# board.net
KiCad netlist of a schematic drawn in EAGLE
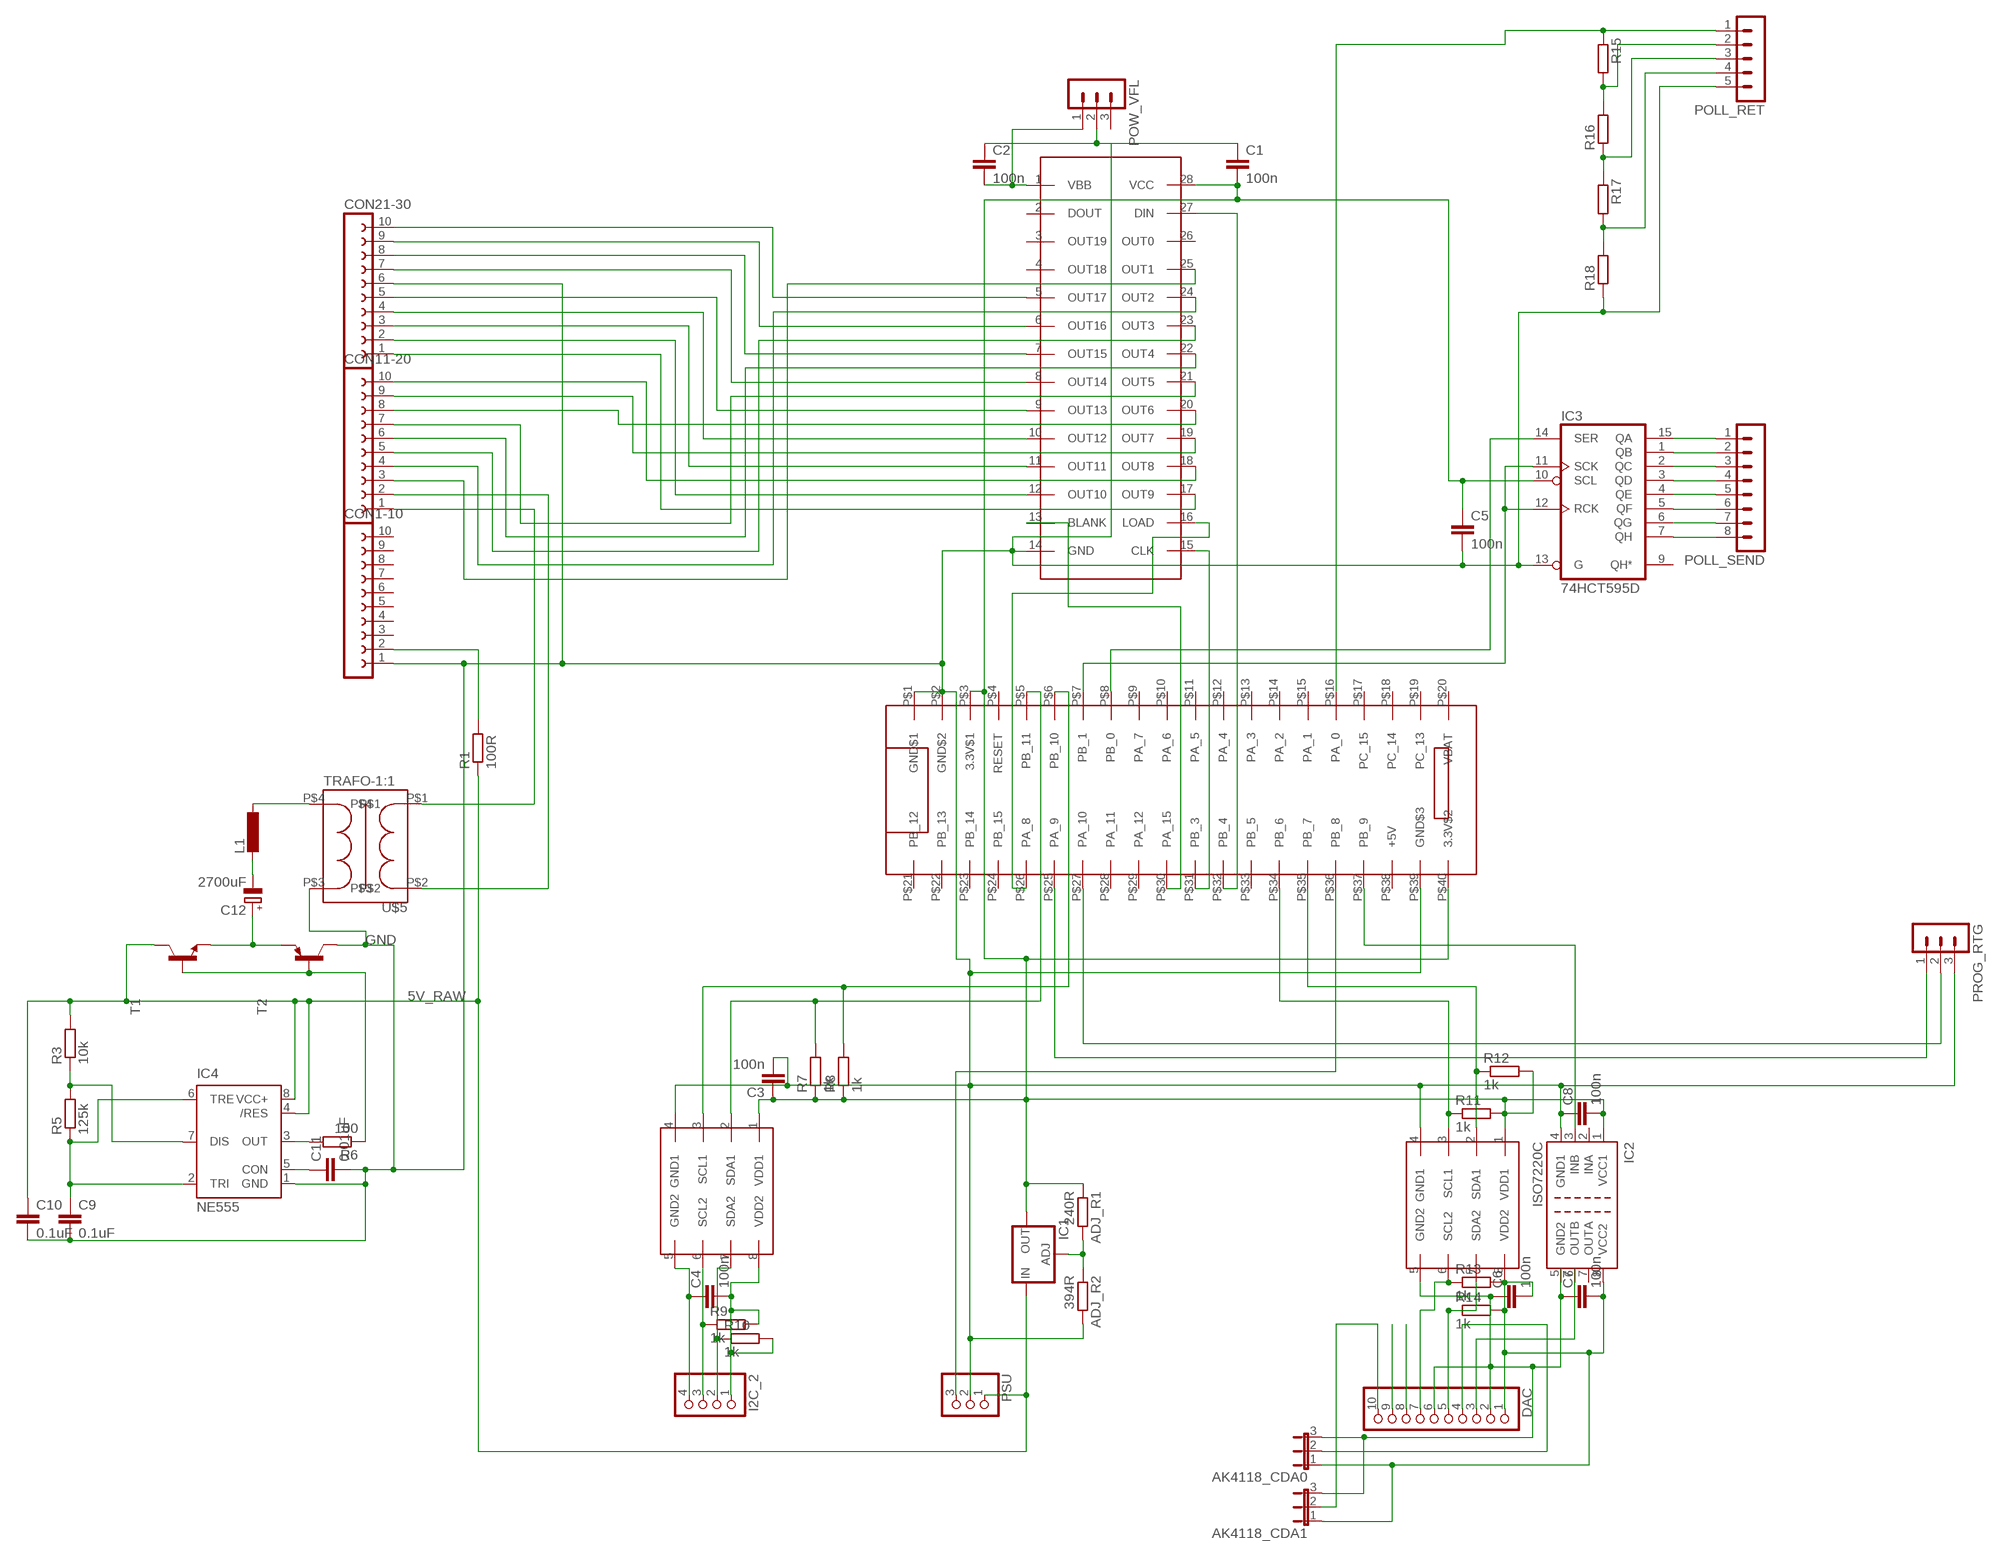
[diagram p0: schematic, sheet 1]

(export (version "E")
  (design (tool "Eeschema 10.0.6"))
  (components
    (comp (ref "ADJ_R1")
      (value "240R")
      (footprint "eagle-import:0207_10")
      (libsource (lib "eagle-import") (part "R-EU_0207/10"))
    )
    (comp (ref "ADJ_R2")
      (value "394R")
      (footprint "eagle-import:0207_10")
      (libsource (lib "eagle-import") (part "R-EU_0207/10"))
    )
    (comp (ref "AK4118_CDA0")
      (value "JP2E")
      (footprint "eagle-import:JP2")
      (libsource (lib "eagle-import") (part "JP2E"))
    )
    (comp (ref "AK4118_CDA1")
      (value "JP2E")
      (footprint "eagle-import:JP2")
      (libsource (lib "eagle-import") (part "JP2E"))
    )
    (comp (ref "C1")
      (value "100n")
      (footprint "eagle-import:C1206")
      (libsource (lib "eagle-import") (part "C-EUC1206"))
    )
    (comp (ref "C2")
      (value "100n")
      (footprint "eagle-import:C1206")
      (libsource (lib "eagle-import") (part "C-EUC1206"))
    )
    (comp (ref "C3")
      (value "100n")
      (footprint "eagle-import:C1206")
      (libsource (lib "eagle-import") (part "C-EUC1206"))
    )
    (comp (ref "C4")
      (value "100n")
      (footprint "eagle-import:C1206")
      (libsource (lib "eagle-import") (part "C-EUC1206"))
    )
    (comp (ref "C5")
      (value "100n")
      (footprint "eagle-import:C1206")
      (libsource (lib "eagle-import") (part "C-EUC1206"))
    )
    (comp (ref "C6")
      (value "100n")
      (footprint "eagle-import:C1206")
      (libsource (lib "eagle-import") (part "C-EUC1206"))
    )
    (comp (ref "C7")
      (value "100n")
      (footprint "eagle-import:C1210")
      (libsource (lib "eagle-import") (part "C-EUC1210"))
    )
    (comp (ref "C8")
      (value "100n")
      (footprint "eagle-import:C1210")
      (libsource (lib "eagle-import") (part "C-EUC1210"))
    )
    (comp (ref "C9")
      (value "0.1uF")
      (footprint "eagle-import:C1206")
      (libsource (lib "eagle-import") (part "C-EUC1206"))
    )
    (comp (ref "C10")
      (value "0.1uF")
      (footprint "eagle-import:C1206")
      (libsource (lib "eagle-import") (part "C-EUC1206"))
    )
    (comp (ref "C11")
      (value "0.01uF")
      (footprint "eagle-import:C1206")
      (libsource (lib "eagle-import") (part "C-EUC1206"))
    )
    (comp (ref "C12")
      (value "2700uF")
      (footprint "eagle-import:E3,5-8")
      (libsource (lib "eagle-import") (part "CPOL-EUE3.5-8"))
    )
    (comp (ref "CON1-10")
      (value "FE10-1")
      (footprint "eagle-import:FE10")
      (libsource (lib "eagle-import") (part "FE10-1"))
    )
    (comp (ref "CON11-20")
      (value "FE10-1")
      (footprint "eagle-import:FE10")
      (libsource (lib "eagle-import") (part "FE10-1"))
    )
    (comp (ref "CON21-30")
      (value "FE10-1")
      (footprint "eagle-import:FE10")
      (libsource (lib "eagle-import") (part "FE10-1"))
    )
    (comp (ref "DAC")
      (value "PINHD-1X10")
      (footprint "eagle-import:1X10")
      (libsource (lib "eagle-import") (part "PINHD-1X10"))
    )
    (comp (ref "I2C_2")
      (value "PINHD-1X4")
      (footprint "eagle-import:1X04")
      (libsource (lib "eagle-import") (part "PINHD-1X4"))
    )
    (comp (ref "IC1")
      (value "LM317TS")
      (footprint "eagle-import:317TS")
      (libsource (lib "eagle-import") (part "LM317TS"))
    )
    (comp (ref "IC2")
      (value "ISO7220C")
      (footprint "eagle-import:SO-08")
      (fields (field (name "MPN") "ISO7220CD"))
      (libsource (lib "eagle-import") (part "ISO7220C"))
    )
    (comp (ref "IC3")
      (value "74HCT595D")
      (footprint "eagle-import:SO16")
      (libsource (lib "eagle-import") (part "74595DHCT"))
    )
    (comp (ref "IC4")
      (value "NE555")
      (footprint "eagle-import:DIL-08")
      (fields (field (name "MF") "Arrow Electronics") (field (name "MPN") "NE555N"))
      (libsource (lib "eagle-import") (part "NE555"))
    )
    (comp (ref "L1")
      (value "L-EU0204/5")
      (footprint "eagle-import:0204_5")
      (libsource (lib "eagle-import") (part "L-EU0204/5"))
    )
    (comp (ref "POLL_RET")
      (value "MA05-1")
      (footprint "eagle-import:MA05-1")
      (libsource (lib "eagle-import") (part "MA05-1"))
    )
    (comp (ref "POLL_SEND")
      (value "MA08-1")
      (footprint "eagle-import:MA08-1")
      (libsource (lib "eagle-import") (part "MA08-1"))
    )
    (comp (ref "POW_VFL")
      (value "MA03-1")
      (footprint "eagle-import:MA03-1")
      (libsource (lib "eagle-import") (part "MA03-1"))
    )
    (comp (ref "PROG_RTG")
      (value "MA03-1")
      (footprint "eagle-import:MA03-1")
      (libsource (lib "eagle-import") (part "MA03-1"))
    )
    (comp (ref "PSU")
      (value "PINHD-1X3")
      (footprint "eagle-import:1X03")
      (libsource (lib "eagle-import") (part "PINHD-1X3"))
    )
    (comp (ref "R1")
      (value "100R")
      (footprint "eagle-import:0207_10")
      (libsource (lib "eagle-import") (part "R-EU_0207/10"))
    )
    (comp (ref "R3")
      (value "10k")
      (footprint "eagle-import:R1206")
      (libsource (lib "eagle-import") (part "R-EU_R1206"))
    )
    (comp (ref "R5")
      (value "125k")
      (footprint "eagle-import:R1206")
      (libsource (lib "eagle-import") (part "R-EU_R1206"))
    )
    (comp (ref "R6")
      (value "100")
      (footprint "eagle-import:R1206")
      (libsource (lib "eagle-import") (part "R-EU_R1206"))
    )
    (comp (ref "R7")
      (value "1k")
      (footprint "eagle-import:M1206")
      (libsource (lib "eagle-import") (part "R-EU_M1206"))
    )
    (comp (ref "R8")
      (value "1k")
      (footprint "eagle-import:M1206")
      (libsource (lib "eagle-import") (part "R-EU_M1206"))
    )
    (comp (ref "R9")
      (value "1k")
      (footprint "eagle-import:M1206")
      (libsource (lib "eagle-import") (part "R-EU_M1206"))
    )
    (comp (ref "R10")
      (value "1k")
      (footprint "eagle-import:M1206")
      (libsource (lib "eagle-import") (part "R-EU_M1206"))
    )
    (comp (ref "R11")
      (value "1k")
      (footprint "eagle-import:M1206")
      (libsource (lib "eagle-import") (part "R-EU_M1206"))
    )
    (comp (ref "R12")
      (value "1k")
      (footprint "eagle-import:M1206")
      (libsource (lib "eagle-import") (part "R-EU_M1206"))
    )
    (comp (ref "R13")
      (value "1k")
      (footprint "eagle-import:M1206")
      (libsource (lib "eagle-import") (part "R-EU_M1206"))
    )
    (comp (ref "R14")
      (value "1k")
      (footprint "eagle-import:M1206")
      (libsource (lib "eagle-import") (part "R-EU_M1206"))
    )
    (comp (ref "R15")
      (value "R-EU_M1206")
      (footprint "eagle-import:M1206")
      (libsource (lib "eagle-import") (part "R-EU_M1206"))
    )
    (comp (ref "R16")
      (value "R-EU_M1206")
      (footprint "eagle-import:M1206")
      (libsource (lib "eagle-import") (part "R-EU_M1206"))
    )
    (comp (ref "R17")
      (value "R-EU_M1206")
      (footprint "eagle-import:M1206")
      (libsource (lib "eagle-import") (part "R-EU_M1206"))
    )
    (comp (ref "R18")
      (value "R-EU_M1206")
      (footprint "eagle-import:M1206")
      (libsource (lib "eagle-import") (part "R-EU_M1206"))
    )
    (comp (ref "T1")
      (value "-NPN-TO92")
      (footprint "eagle-import:TO92")
      (libsource (lib "eagle-import") (part "-NPN-TO92"))
    )
    (comp (ref "T2")
      (value "-PNP-TO92")
      (footprint "eagle-import:TO92")
      (libsource (lib "eagle-import") (part "-PNP-TO92"))
    )
    (comp (ref "U$1")
      (value "ADUM1250")
      (footprint "eagle-import:SO8")
      (libsource (lib "eagle-import") (part "ADUM1250"))
    )
    (comp (ref "U$2")
      (value "ADUM1250")
      (footprint "eagle-import:SO8")
      (libsource (lib "eagle-import") (part "ADUM1250"))
    )
    (comp (ref "U$3")
      (value "STM32F103C8T6_BOARD")
      (footprint "eagle-import:STM32F103C8T6_BOARD")
      (libsource (lib "eagle-import") (part "STM32F103C8T6_BOARD"))
    )
    (comp (ref "U$4")
      (value "MAX6921AWI")
      (footprint "eagle-import:SO28L")
      (libsource (lib "eagle-import") (part "MAX6921AWI"))
    )
    (comp (ref "U$5")
      (value "TRAFO-1:1")
      (footprint "eagle-import:TRAFO-10-12.5")
      (libsource (lib "eagle-import") (part "TRAFO-1{colon}1"))
    )
  )
  (nets
    (net (code "1") (name "/5V_RAW") (class "Default")
      (node (ref "C10") (pin "1") (pinfunction "1_1") (pintype "passive"))
      (node (ref "IC1") (pin "3") (pinfunction "IN_3") (pintype "input"))
      (node (ref "IC4") (pin "4") (pinfunction "/RES_4") (pintype "input"))
      (node (ref "IC4") (pin "8") (pinfunction "VCC+_8") (pintype "power_in"))
      (node (ref "PSU") (pin "1") (pinfunction "1_1") (pintype "passive"))
      (node (ref "R1") (pin "1") (pinfunction "1_1") (pintype "passive"))
      (node (ref "R3") (pin "2") (pinfunction "2_2") (pintype "passive"))
      (node (ref "T1") (pin "3") (pinfunction "C_3") (pintype "passive"))
    )
    (net (code "2") (name "/GND") (class "Default")
      (node (ref "ADJ_R2") (pin "2") (pinfunction "2_2") (pintype "passive"))
      (node (ref "C1") (pin "1") (pinfunction "1_1") (pintype "passive"))
      (node (ref "C10") (pin "2") (pinfunction "2_2") (pintype "passive"))
      (node (ref "C11") (pin "2") (pinfunction "2_2") (pintype "passive"))
      (node (ref "C2") (pin "1") (pinfunction "1_1") (pintype "passive"))
      (node (ref "C3") (pin "2") (pinfunction "2_2") (pintype "passive"))
      (node (ref "C5") (pin "2") (pinfunction "2_2") (pintype "passive"))
      (node (ref "C8") (pin "1") (pinfunction "1_1") (pintype "passive"))
      (node (ref "C9") (pin "2") (pinfunction "2_2") (pintype "passive"))
      (node (ref "CON1-10") (pin "1") (pinfunction "1_1") (pintype "passive"))
      (node (ref "CON21-30") (pin "6") (pinfunction "6_6") (pintype "passive"))
      (node (ref "IC2") (pin "4") (pinfunction "GND1_4") (pintype "power_in"))
      (node (ref "IC3") (pin "13") (pinfunction "G_13") (pintype "input"))
      (node (ref "IC4") (pin "1") (pinfunction "GND_1") (pintype "power_in"))
      (node (ref "POLL_RET") (pin "5") (pinfunction "5_5") (pintype "passive"))
      (node (ref "POW_VFL") (pin "2") (pinfunction "2_2") (pintype "passive"))
      (node (ref "PROG_RTG") (pin "3") (pinfunction "3_3") (pintype "passive"))
      (node (ref "PSU") (pin "2") (pinfunction "2_2") (pintype "passive"))
      (node (ref "R18") (pin "1") (pinfunction "1_1") (pintype "passive"))
      (node (ref "T2") (pin "3") (pinfunction "C_3") (pintype "passive"))
      (node (ref "U$1") (pin "4") (pinfunction "GND1_4") (pintype "bidirectional"))
      (node (ref "U$2") (pin "4") (pinfunction "GND1_4") (pintype "bidirectional"))
      (node (ref "U$3") (pin "P$1") (pinfunction "GND$1_P$1") (pintype "bidirectional"))
      (node (ref "U$3") (pin "P$2") (pinfunction "GND$2_P$2") (pintype "bidirectional"))
      (node (ref "U$3") (pin "P$39") (pinfunction "GND$3_P$39") (pintype "bidirectional"))
      (node (ref "U$4") (pin "14") (pinfunction "GND_14") (pintype "bidirectional"))
      (node (ref "U$5") (pin "P$3") (pinfunction "P$3_P$3") (pintype "bidirectional"))
    )
    (net (code "3") (name "Net-(AK4118_CDA0-Pad2)") (class "Default")
      (node (ref "AK4118_CDA0") (pin "2") (pinfunction "2_2") (pintype "passive"))
      (node (ref "DAC") (pin "4") (pinfunction "4_4") (pintype "passive"))
    )
    (net (code "4") (name "Net-(AK4118_CDA1-Pad2)") (class "Default")
      (node (ref "AK4118_CDA1") (pin "2") (pinfunction "2_2") (pintype "passive"))
      (node (ref "DAC") (pin "10") (pinfunction "10_10") (pintype "passive"))
    )
    (net (code "5") (name "Net-(C12-Pad-)") (class "Default")
      (node (ref "C12") (pin "-") (pinfunction "-_-") (pintype "passive"))
      (node (ref "L1") (pin "2") (pinfunction "2_2") (pintype "passive"))
    )
    (net (code "6") (name "Net-(CON1-10-Pad2)") (class "Default")
      (node (ref "CON1-10") (pin "2") (pinfunction "2_2") (pintype "passive"))
      (node (ref "R1") (pin "2") (pinfunction "2_2") (pintype "passive"))
    )
    (net (code "7") (name "Net-(CON11-20-Pad1)") (class "Default")
      (node (ref "CON11-20") (pin "1") (pinfunction "1_1") (pintype "passive"))
      (node (ref "U$5") (pin "P$1") (pinfunction "P$1_P$1") (pintype "bidirectional"))
    )
    (net (code "8") (name "Net-(CON11-20-Pad2)") (class "Default")
      (node (ref "CON11-20") (pin "2") (pinfunction "2_2") (pintype "passive"))
      (node (ref "U$5") (pin "P$2") (pinfunction "P$2_P$2") (pintype "bidirectional"))
    )
    (net (code "9") (name "Net-(IC1-ADJ)") (class "Default")
      (node (ref "ADJ_R1") (pin "2") (pinfunction "2_2") (pintype "passive"))
      (node (ref "ADJ_R2") (pin "1") (pinfunction "1_1") (pintype "passive"))
      (node (ref "IC1") (pin "1") (pinfunction "ADJ_1") (pintype "input"))
    )
    (net (code "10") (name "Net-(IC1-OUT)") (class "Default")
      (node (ref "ADJ_R1") (pin "1") (pinfunction "1_1") (pintype "passive"))
      (node (ref "C1") (pin "2") (pinfunction "2_2") (pintype "passive"))
      (node (ref "C3") (pin "1") (pinfunction "1_1") (pintype "passive"))
      (node (ref "C5") (pin "1") (pinfunction "1_1") (pintype "passive"))
      (node (ref "C8") (pin "2") (pinfunction "2_2") (pintype "passive"))
      (node (ref "IC1") (pin "2") (pinfunction "OUT_2") (pintype "passive"))
      (node (ref "IC2") (pin "1") (pinfunction "VCC1_1") (pintype "power_in"))
      (node (ref "IC3") (pin "10") (pinfunction "SCL_10") (pintype "input"))
      (node (ref "R11") (pin "2") (pinfunction "2_2") (pintype "passive"))
      (node (ref "R12") (pin "2") (pinfunction "2_2") (pintype "passive"))
      (node (ref "R7") (pin "1") (pinfunction "1_1") (pintype "passive"))
      (node (ref "R8") (pin "1") (pinfunction "1_1") (pintype "passive"))
      (node (ref "U$1") (pin "1") (pinfunction "VDD1_1") (pintype "bidirectional"))
      (node (ref "U$2") (pin "1") (pinfunction "VDD1_1") (pintype "bidirectional"))
      (node (ref "U$3") (pin "P$3") (pinfunction "3.3V$1_P$3") (pintype "bidirectional"))
      (node (ref "U$3") (pin "P$40") (pinfunction "3.3V$2_P$40") (pintype "bidirectional"))
      (node (ref "U$4") (pin "28") (pinfunction "VCC_28") (pintype "bidirectional"))
    )
    (net (code "11") (name "Net-(IC2-GND2)") (class "Default")
      (node (ref "AK4118_CDA0") (pin "3") (pinfunction "3_3") (pintype "passive"))
      (node (ref "AK4118_CDA1") (pin "3") (pinfunction "3_3") (pintype "passive"))
      (node (ref "C6") (pin "1") (pinfunction "1_1") (pintype "passive"))
      (node (ref "C7") (pin "1") (pinfunction "1_1") (pintype "passive"))
      (node (ref "DAC") (pin "2") (pinfunction "2_2") (pintype "passive"))
      (node (ref "DAC") (pin "6") (pinfunction "6_6") (pintype "passive"))
      (node (ref "IC2") (pin "5") (pinfunction "GND2_5") (pintype "power_in"))
      (node (ref "U$1") (pin "5") (pinfunction "GND2_5") (pintype "bidirectional"))
    )
    (net (code "12") (name "Net-(IC2-INB)") (class "Default")
      (node (ref "IC2") (pin "3") (pinfunction "INB_3") (pintype "input"))
      (node (ref "U$3") (pin "P$37") (pinfunction "PB_9_P$37") (pintype "bidirectional"))
    )
    (net (code "13") (name "Net-(IC2-OUTB)") (class "Default")
      (node (ref "DAC") (pin "3") (pinfunction "3_3") (pintype "passive"))
      (node (ref "IC2") (pin "6") (pinfunction "OUTB_6") (pintype "output"))
    )
    (net (code "14") (name "Net-(IC2-VCC2)") (class "Default")
      (node (ref "AK4118_CDA0") (pin "1") (pinfunction "1_1") (pintype "passive"))
      (node (ref "AK4118_CDA1") (pin "1") (pinfunction "1_1") (pintype "passive"))
      (node (ref "C6") (pin "2") (pinfunction "2_2") (pintype "passive"))
      (node (ref "C7") (pin "2") (pinfunction "2_2") (pintype "passive"))
      (node (ref "DAC") (pin "1") (pinfunction "1_1") (pintype "passive"))
      (node (ref "IC2") (pin "8") (pinfunction "VCC2_8") (pintype "power_in"))
      (node (ref "R13") (pin "2") (pinfunction "2_2") (pintype "passive"))
      (node (ref "R14") (pin "2") (pinfunction "2_2") (pintype "passive"))
      (node (ref "U$1") (pin "8") (pinfunction "VDD2_8") (pintype "bidirectional"))
    )
    (net (code "15") (name "Net-(IC3A-QA)") (class "Default")
      (node (ref "IC3") (pin "15") (pinfunction "QA_15") (pintype "tri_state"))
      (node (ref "POLL_SEND") (pin "1") (pinfunction "1_1") (pintype "passive"))
    )
    (net (code "16") (name "Net-(IC3A-QB)") (class "Default")
      (node (ref "IC3") (pin "1") (pinfunction "QB_1") (pintype "tri_state"))
      (node (ref "POLL_SEND") (pin "2") (pinfunction "2_2") (pintype "passive"))
    )
    (net (code "17") (name "Net-(IC3A-QC)") (class "Default")
      (node (ref "IC3") (pin "2") (pinfunction "QC_2") (pintype "tri_state"))
      (node (ref "POLL_SEND") (pin "3") (pinfunction "3_3") (pintype "passive"))
    )
    (net (code "18") (name "Net-(IC3A-QD)") (class "Default")
      (node (ref "IC3") (pin "3") (pinfunction "QD_3") (pintype "tri_state"))
      (node (ref "POLL_SEND") (pin "4") (pinfunction "4_4") (pintype "passive"))
    )
    (net (code "19") (name "Net-(IC3A-QE)") (class "Default")
      (node (ref "IC3") (pin "4") (pinfunction "QE_4") (pintype "tri_state"))
      (node (ref "POLL_SEND") (pin "5") (pinfunction "5_5") (pintype "passive"))
    )
    (net (code "20") (name "Net-(IC3A-QF)") (class "Default")
      (node (ref "IC3") (pin "5") (pinfunction "QF_5") (pintype "tri_state"))
      (node (ref "POLL_SEND") (pin "6") (pinfunction "6_6") (pintype "passive"))
    )
    (net (code "21") (name "Net-(IC3A-QG)") (class "Default")
      (node (ref "IC3") (pin "6") (pinfunction "QG_6") (pintype "tri_state"))
      (node (ref "POLL_SEND") (pin "7") (pinfunction "7_7") (pintype "passive"))
    )
    (net (code "22") (name "Net-(IC3A-QH)") (class "Default")
      (node (ref "IC3") (pin "7") (pinfunction "QH_7") (pintype "tri_state"))
      (node (ref "POLL_SEND") (pin "8") (pinfunction "8_8") (pintype "passive"))
    )
    (net (code "23") (name "Net-(IC3A-RCK)") (class "Default")
      (node (ref "IC3") (pin "11") (pinfunction "SCK_11") (pintype "input"))
      (node (ref "IC3") (pin "12") (pinfunction "RCK_12") (pintype "input"))
      (node (ref "U$3") (pin "P$7") (pinfunction "PB_1_P$7") (pintype "bidirectional"))
    )
    (net (code "24") (name "Net-(IC3A-SER)") (class "Default")
      (node (ref "IC3") (pin "14") (pinfunction "SER_14") (pintype "input"))
      (node (ref "U$3") (pin "P$8") (pinfunction "PB_0_P$8") (pintype "bidirectional"))
    )
    (net (code "25") (name "Net-(IC4-CON)") (class "Default")
      (node (ref "C11") (pin "1") (pinfunction "1_1") (pintype "passive"))
      (node (ref "IC4") (pin "5") (pinfunction "CON_5") (pintype "input"))
    )
    (net (code "26") (name "Net-(IC4-DIS)") (class "Default")
      (node (ref "IC4") (pin "7") (pinfunction "DIS_7") (pintype "input"))
      (node (ref "R3") (pin "1") (pinfunction "1_1") (pintype "passive"))
      (node (ref "R5") (pin "2") (pinfunction "2_2") (pintype "passive"))
    )
    (net (code "27") (name "Net-(IC4-OUT)") (class "Default")
      (node (ref "IC4") (pin "3") (pinfunction "OUT_3") (pintype "output"))
      (node (ref "R6") (pin "2") (pinfunction "2_2") (pintype "passive"))
    )
    (net (code "28") (name "Net-(IC4-TRE)") (class "Default")
      (node (ref "C9") (pin "1") (pinfunction "1_1") (pintype "passive"))
      (node (ref "IC4") (pin "2") (pinfunction "TRI_2") (pintype "input"))
      (node (ref "IC4") (pin "6") (pinfunction "TRE_6") (pintype "input"))
      (node (ref "R5") (pin "1") (pinfunction "1_1") (pintype "passive"))
    )
    (net (code "29") (name "Net-(L1-Pad1)") (class "Default")
      (node (ref "L1") (pin "1") (pinfunction "1_1") (pintype "passive"))
      (node (ref "U$5") (pin "P$4") (pinfunction "P$4_P$4") (pintype "bidirectional"))
    )
    (net (code "30") (name "Net-(POLL_RET-Pad2)") (class "Default")
      (node (ref "POLL_RET") (pin "2") (pinfunction "2_2") (pintype "passive"))
      (node (ref "R15") (pin "2") (pinfunction "2_2") (pintype "passive"))
      (node (ref "R16") (pin "2") (pinfunction "2_2") (pintype "passive"))
    )
    (net (code "31") (name "Net-(POLL_RET-Pad3)") (class "Default")
      (node (ref "POLL_RET") (pin "3") (pinfunction "3_3") (pintype "passive"))
      (node (ref "R16") (pin "1") (pinfunction "1_1") (pintype "passive"))
      (node (ref "R17") (pin "1") (pinfunction "1_1") (pintype "passive"))
    )
    (net (code "32") (name "Net-(POLL_RET-Pad4)") (class "Default")
      (node (ref "POLL_RET") (pin "4") (pinfunction "4_4") (pintype "passive"))
      (node (ref "R17") (pin "2") (pinfunction "2_2") (pintype "passive"))
      (node (ref "R18") (pin "2") (pinfunction "2_2") (pintype "passive"))
    )
    (net (code "33") (name "Net-(T1-B)") (class "Default")
      (node (ref "R6") (pin "1") (pinfunction "1_1") (pintype "passive"))
      (node (ref "T1") (pin "2") (pinfunction "B_2") (pintype "passive"))
      (node (ref "T2") (pin "2") (pinfunction "B_2") (pintype "passive"))
    )
    (net (code "34") (name "Net-(T1-E)") (class "Default")
      (node (ref "C12") (pin "+") (pinfunction "+_+") (pintype "passive"))
      (node (ref "T1") (pin "1") (pinfunction "E_1") (pintype "passive"))
      (node (ref "T2") (pin "1") (pinfunction "E_1") (pintype "passive"))
    )
    (net (code "35") (name "Net-(U$1-SCL1)") (class "Default")
      (node (ref "R11") (pin "1") (pinfunction "1_1") (pintype "passive"))
      (node (ref "U$1") (pin "3") (pinfunction "SCL1_3") (pintype "bidirectional"))
      (node (ref "U$3") (pin "P$34") (pinfunction "PB_6_P$34") (pintype "bidirectional"))
    )
    (net (code "36") (name "Net-(U$1-SCL2)") (class "Default")
      (node (ref "DAC") (pin "7") (pinfunction "7_7") (pintype "passive"))
      (node (ref "R13") (pin "1") (pinfunction "1_1") (pintype "passive"))
      (node (ref "U$1") (pin "6") (pinfunction "SCL2_6") (pintype "bidirectional"))
    )
    (net (code "37") (name "Net-(U$1-SDA1)") (class "Default")
      (node (ref "R12") (pin "1") (pinfunction "1_1") (pintype "passive"))
      (node (ref "U$1") (pin "2") (pinfunction "SDA1_2") (pintype "bidirectional"))
      (node (ref "U$3") (pin "P$35") (pinfunction "PB_7_P$35") (pintype "bidirectional"))
    )
    (net (code "38") (name "Net-(U$1-SDA2)") (class "Default")
      (node (ref "DAC") (pin "5") (pinfunction "5_5") (pintype "passive"))
      (node (ref "R14") (pin "1") (pinfunction "1_1") (pintype "passive"))
      (node (ref "U$1") (pin "7") (pinfunction "SDA2_7") (pintype "bidirectional"))
    )
    (net (code "39") (name "Net-(U$2-GND2)") (class "Default")
      (node (ref "C4") (pin "1") (pinfunction "1_1") (pintype "passive"))
      (node (ref "I2C_2") (pin "4") (pinfunction "4_4") (pintype "passive"))
      (node (ref "U$2") (pin "5") (pinfunction "GND2_5") (pintype "bidirectional"))
    )
    (net (code "40") (name "Net-(U$2-SCL1)") (class "Default")
      (node (ref "R8") (pin "2") (pinfunction "2_2") (pintype "passive"))
      (node (ref "U$2") (pin "3") (pinfunction "SCL1_3") (pintype "bidirectional"))
      (node (ref "U$3") (pin "P$6") (pinfunction "PB_10_P$6") (pintype "bidirectional"))
    )
    (net (code "41") (name "Net-(U$2-SCL2)") (class "Default")
      (node (ref "I2C_2") (pin "3") (pinfunction "3_3") (pintype "passive"))
      (node (ref "R9") (pin "1") (pinfunction "1_1") (pintype "passive"))
      (node (ref "U$2") (pin "6") (pinfunction "SCL2_6") (pintype "bidirectional"))
    )
    (net (code "42") (name "Net-(U$2-SDA1)") (class "Default")
      (node (ref "R7") (pin "2") (pinfunction "2_2") (pintype "passive"))
      (node (ref "U$2") (pin "2") (pinfunction "SDA1_2") (pintype "bidirectional"))
      (node (ref "U$3") (pin "P$5") (pinfunction "PB_11_P$5") (pintype "bidirectional"))
    )
    (net (code "43") (name "Net-(U$2-SDA2)") (class "Default")
      (node (ref "I2C_2") (pin "2") (pinfunction "2_2") (pintype "passive"))
      (node (ref "R10") (pin "1") (pinfunction "1_1") (pintype "passive"))
      (node (ref "U$2") (pin "7") (pinfunction "SDA2_7") (pintype "bidirectional"))
    )
    (net (code "44") (name "Net-(U$2-VDD2)") (class "Default")
      (node (ref "C4") (pin "2") (pinfunction "2_2") (pintype "passive"))
      (node (ref "I2C_2") (pin "1") (pinfunction "1_1") (pintype "passive"))
      (node (ref "R10") (pin "2") (pinfunction "2_2") (pintype "passive"))
      (node (ref "R9") (pin "2") (pinfunction "2_2") (pintype "passive"))
      (node (ref "U$2") (pin "8") (pinfunction "VDD2_8") (pintype "bidirectional"))
    )
    (net (code "45") (name "Net-(U$3-PA_0)") (class "Default")
      (node (ref "POLL_RET") (pin "1") (pinfunction "1_1") (pintype "passive"))
      (node (ref "R15") (pin "1") (pinfunction "1_1") (pintype "passive"))
      (node (ref "U$3") (pin "P$16") (pinfunction "PA_0_P$16") (pintype "bidirectional"))
    )
    (net (code "46") (name "Net-(U$3-PA_8)") (class "Default")
      (node (ref "U$3") (pin "P$26") (pinfunction "PA_8_P$26") (pintype "bidirectional"))
      (node (ref "U$4") (pin "16") (pinfunction "LOAD_16") (pintype "bidirectional"))
    )
    (net (code "47") (name "Net-(U$3-PA_9)") (class "Default")
      (node (ref "PROG_RTG") (pin "1") (pinfunction "1_1") (pintype "passive"))
      (node (ref "U$3") (pin "P$25") (pinfunction "PA_9_P$25") (pintype "bidirectional"))
    )
    (net (code "48") (name "Net-(U$3-PA_10)") (class "Default")
      (node (ref "PROG_RTG") (pin "2") (pinfunction "2_2") (pintype "passive"))
      (node (ref "U$3") (pin "P$27") (pinfunction "PA_10_P$27") (pintype "bidirectional"))
    )
    (net (code "49") (name "Net-(U$3-PA_15)") (class "Default")
      (node (ref "U$3") (pin "P$30") (pinfunction "PA_15_P$30") (pintype "bidirectional"))
      (node (ref "U$4") (pin "13") (pinfunction "BLANK_13") (pintype "bidirectional"))
    )
    (net (code "50") (name "Net-(U$3-PB_3)") (class "Default")
      (node (ref "U$3") (pin "P$31") (pinfunction "PB_3_P$31") (pintype "bidirectional"))
      (node (ref "U$4") (pin "15") (pinfunction "CLK_15") (pintype "bidirectional"))
    )
    (net (code "51") (name "Net-(U$3-PB_4)") (class "Default")
      (node (ref "U$3") (pin "P$32") (pinfunction "PB_4_P$32") (pintype "bidirectional"))
      (node (ref "U$4") (pin "27") (pinfunction "DIN_27") (pintype "bidirectional"))
    )
    (net (code "52") (name "Net-(U$3-PB_8)") (class "Default")
      (node (ref "PSU") (pin "3") (pinfunction "3_3") (pintype "passive"))
      (node (ref "U$3") (pin "P$36") (pinfunction "PB_8_P$36") (pintype "bidirectional"))
    )
    (net (code "53") (name "Net-(U$4-OUT1)") (class "Default")
      (node (ref "CON11-20") (pin "3") (pinfunction "3_3") (pintype "passive"))
      (node (ref "U$4") (pin "25") (pinfunction "OUT1_25") (pintype "bidirectional"))
    )
    (net (code "54") (name "Net-(U$4-OUT2)") (class "Default")
      (node (ref "CON11-20") (pin "4") (pinfunction "4_4") (pintype "passive"))
      (node (ref "U$4") (pin "24") (pinfunction "OUT2_24") (pintype "bidirectional"))
    )
    (net (code "55") (name "Net-(U$4-OUT3)") (class "Default")
      (node (ref "CON11-20") (pin "5") (pinfunction "5_5") (pintype "passive"))
      (node (ref "U$4") (pin "23") (pinfunction "OUT3_23") (pintype "bidirectional"))
    )
    (net (code "56") (name "Net-(U$4-OUT4)") (class "Default")
      (node (ref "CON11-20") (pin "6") (pinfunction "6_6") (pintype "passive"))
      (node (ref "U$4") (pin "22") (pinfunction "OUT4_22") (pintype "bidirectional"))
    )
    (net (code "57") (name "Net-(U$4-OUT5)") (class "Default")
      (node (ref "CON11-20") (pin "7") (pinfunction "7_7") (pintype "passive"))
      (node (ref "U$4") (pin "21") (pinfunction "OUT5_21") (pintype "bidirectional"))
    )
    (net (code "58") (name "Net-(U$4-OUT6)") (class "Default")
      (node (ref "CON11-20") (pin "8") (pinfunction "8_8") (pintype "passive"))
      (node (ref "U$4") (pin "20") (pinfunction "OUT6_20") (pintype "bidirectional"))
    )
    (net (code "59") (name "Net-(U$4-OUT7)") (class "Default")
      (node (ref "CON11-20") (pin "9") (pinfunction "9_9") (pintype "passive"))
      (node (ref "U$4") (pin "19") (pinfunction "OUT7_19") (pintype "bidirectional"))
    )
    (net (code "60") (name "Net-(U$4-OUT8)") (class "Default")
      (node (ref "CON11-20") (pin "10") (pinfunction "10_10") (pintype "passive"))
      (node (ref "U$4") (pin "18") (pinfunction "OUT8_18") (pintype "bidirectional"))
    )
    (net (code "61") (name "Net-(U$4-OUT9)") (class "Default")
      (node (ref "CON21-30") (pin "1") (pinfunction "1_1") (pintype "passive"))
      (node (ref "U$4") (pin "17") (pinfunction "OUT9_17") (pintype "bidirectional"))
    )
    (net (code "62") (name "Net-(U$4-OUT10)") (class "Default")
      (node (ref "CON21-30") (pin "2") (pinfunction "2_2") (pintype "passive"))
      (node (ref "U$4") (pin "12") (pinfunction "OUT10_12") (pintype "bidirectional"))
    )
    (net (code "63") (name "Net-(U$4-OUT11)") (class "Default")
      (node (ref "CON21-30") (pin "3") (pinfunction "3_3") (pintype "passive"))
      (node (ref "U$4") (pin "11") (pinfunction "OUT11_11") (pintype "bidirectional"))
    )
    (net (code "64") (name "Net-(U$4-OUT12)") (class "Default")
      (node (ref "CON21-30") (pin "4") (pinfunction "4_4") (pintype "passive"))
      (node (ref "U$4") (pin "10") (pinfunction "OUT12_10") (pintype "bidirectional"))
    )
    (net (code "65") (name "Net-(U$4-OUT13)") (class "Default")
      (node (ref "CON21-30") (pin "5") (pinfunction "5_5") (pintype "passive"))
      (node (ref "U$4") (pin "9") (pinfunction "OUT13_9") (pintype "bidirectional"))
    )
    (net (code "66") (name "Net-(U$4-OUT14)") (class "Default")
      (node (ref "CON21-30") (pin "7") (pinfunction "7_7") (pintype "passive"))
      (node (ref "U$4") (pin "8") (pinfunction "OUT14_8") (pintype "bidirectional"))
    )
    (net (code "67") (name "Net-(U$4-OUT15)") (class "Default")
      (node (ref "CON21-30") (pin "8") (pinfunction "8_8") (pintype "passive"))
      (node (ref "U$4") (pin "7") (pinfunction "OUT15_7") (pintype "bidirectional"))
    )
    (net (code "68") (name "Net-(U$4-OUT16)") (class "Default")
      (node (ref "CON21-30") (pin "9") (pinfunction "9_9") (pintype "passive"))
      (node (ref "U$4") (pin "6") (pinfunction "OUT16_6") (pintype "bidirectional"))
    )
    (net (code "69") (name "Net-(U$4-OUT17)") (class "Default")
      (node (ref "CON21-30") (pin "10") (pinfunction "10_10") (pintype "passive"))
      (node (ref "U$4") (pin "5") (pinfunction "OUT17_5") (pintype "bidirectional"))
    )
    (net (code "70") (name "Net-(U$4-VBB)") (class "Default")
      (node (ref "C2") (pin "2") (pinfunction "2_2") (pintype "passive"))
      (node (ref "POW_VFL") (pin "1") (pinfunction "1_1") (pintype "passive"))
      (node (ref "U$4") (pin "1") (pinfunction "VBB_1") (pintype "bidirectional"))
    )
    (net (code "71") (name "unconnected-(CON1-10-Pad3)") (class "Default")
      (node (ref "CON1-10") (pin "3") (pinfunction "3_3") (pintype "passive"))
    )
    (net (code "72") (name "unconnected-(CON1-10-Pad4)") (class "Default")
      (node (ref "CON1-10") (pin "4") (pinfunction "4_4") (pintype "passive"))
    )
    (net (code "73") (name "unconnected-(CON1-10-Pad5)") (class "Default")
      (node (ref "CON1-10") (pin "5") (pinfunction "5_5") (pintype "passive"))
    )
    (net (code "74") (name "unconnected-(CON1-10-Pad6)") (class "Default")
      (node (ref "CON1-10") (pin "6") (pinfunction "6_6") (pintype "passive"))
    )
    (net (code "75") (name "unconnected-(CON1-10-Pad7)") (class "Default")
      (node (ref "CON1-10") (pin "7") (pinfunction "7_7") (pintype "passive"))
    )
    (net (code "76") (name "unconnected-(CON1-10-Pad8)") (class "Default")
      (node (ref "CON1-10") (pin "8") (pinfunction "8_8") (pintype "passive"))
    )
    (net (code "77") (name "unconnected-(CON1-10-Pad9)") (class "Default")
      (node (ref "CON1-10") (pin "9") (pinfunction "9_9") (pintype "passive"))
    )
    (net (code "78") (name "unconnected-(CON1-10-Pad10)") (class "Default")
      (node (ref "CON1-10") (pin "10") (pinfunction "10_10") (pintype "passive"))
    )
    (net (code "79") (name "unconnected-(DAC-Pad8)") (class "Default")
      (node (ref "DAC") (pin "8") (pinfunction "8_8") (pintype "passive"))
    )
    (net (code "80") (name "unconnected-(DAC-Pad9)") (class "Default")
      (node (ref "DAC") (pin "9") (pinfunction "9_9") (pintype "passive"))
    )
    (net (code "81") (name "unconnected-(IC2-INA-Pad2)") (class "Default")
      (node (ref "IC2") (pin "2") (pinfunction "INA_2") (pintype "input"))
    )
    (net (code "82") (name "unconnected-(IC2-OUTA-Pad7)") (class "Default")
      (node (ref "IC2") (pin "7") (pinfunction "OUTA_7") (pintype "output"))
    )
    (net (code "83") (name "unconnected-(IC3A-QH*-Pad9)") (class "Default")
      (node (ref "IC3") (pin "9") (pinfunction "QH*_9") (pintype "tri_state"))
    )
    (net (code "84") (name "unconnected-(POW_VFL-Pad3)") (class "Default")
      (node (ref "POW_VFL") (pin "3") (pinfunction "3_3") (pintype "passive"))
    )
    (net (code "85") (name "unconnected-(U$3-+5V-PadP$38)") (class "Default")
      (node (ref "U$3") (pin "P$38") (pinfunction "+5V_P$38") (pintype "bidirectional"))
    )
    (net (code "86") (name "unconnected-(U$3-PA_1-PadP$15)") (class "Default")
      (node (ref "U$3") (pin "P$15") (pinfunction "PA_1_P$15") (pintype "bidirectional"))
    )
    (net (code "87") (name "unconnected-(U$3-PA_2-PadP$14)") (class "Default")
      (node (ref "U$3") (pin "P$14") (pinfunction "PA_2_P$14") (pintype "bidirectional"))
    )
    (net (code "88") (name "unconnected-(U$3-PA_3-PadP$13)") (class "Default")
      (node (ref "U$3") (pin "P$13") (pinfunction "PA_3_P$13") (pintype "bidirectional"))
    )
    (net (code "89") (name "unconnected-(U$3-PA_4-PadP$12)") (class "Default")
      (node (ref "U$3") (pin "P$12") (pinfunction "PA_4_P$12") (pintype "bidirectional"))
    )
    (net (code "90") (name "unconnected-(U$3-PA_5-PadP$11)") (class "Default")
      (node (ref "U$3") (pin "P$11") (pinfunction "PA_5_P$11") (pintype "bidirectional"))
    )
    (net (code "91") (name "unconnected-(U$3-PA_6-PadP$10)") (class "Default")
      (node (ref "U$3") (pin "P$10") (pinfunction "PA_6_P$10") (pintype "bidirectional"))
    )
    (net (code "92") (name "unconnected-(U$3-PA_7-PadP$9)") (class "Default")
      (node (ref "U$3") (pin "P$9") (pinfunction "PA_7_P$9") (pintype "bidirectional"))
    )
    (net (code "93") (name "unconnected-(U$3-PA_11-PadP$28)") (class "Default")
      (node (ref "U$3") (pin "P$28") (pinfunction "PA_11_P$28") (pintype "bidirectional"))
    )
    (net (code "94") (name "unconnected-(U$3-PA_12-PadP$29)") (class "Default")
      (node (ref "U$3") (pin "P$29") (pinfunction "PA_12_P$29") (pintype "bidirectional"))
    )
    (net (code "95") (name "unconnected-(U$3-PB_5-PadP$33)") (class "Default")
      (node (ref "U$3") (pin "P$33") (pinfunction "PB_5_P$33") (pintype "bidirectional"))
    )
    (net (code "96") (name "unconnected-(U$3-PB_12-PadP$21)") (class "Default")
      (node (ref "U$3") (pin "P$21") (pinfunction "PB_12_P$21") (pintype "bidirectional"))
    )
    (net (code "97") (name "unconnected-(U$3-PB_13-PadP$22)") (class "Default")
      (node (ref "U$3") (pin "P$22") (pinfunction "PB_13_P$22") (pintype "bidirectional"))
    )
    (net (code "98") (name "unconnected-(U$3-PB_14-PadP$23)") (class "Default")
      (node (ref "U$3") (pin "P$23") (pinfunction "PB_14_P$23") (pintype "bidirectional"))
    )
    (net (code "99") (name "unconnected-(U$3-PB_15-PadP$24)") (class "Default")
      (node (ref "U$3") (pin "P$24") (pinfunction "PB_15_P$24") (pintype "bidirectional"))
    )
    (net (code "100") (name "unconnected-(U$3-PC_13-PadP$19)") (class "Default")
      (node (ref "U$3") (pin "P$19") (pinfunction "PC_13_P$19") (pintype "bidirectional"))
    )
    (net (code "101") (name "unconnected-(U$3-PC_14-PadP$18)") (class "Default")
      (node (ref "U$3") (pin "P$18") (pinfunction "PC_14_P$18") (pintype "bidirectional"))
    )
    (net (code "102") (name "unconnected-(U$3-PC_15-PadP$17)") (class "Default")
      (node (ref "U$3") (pin "P$17") (pinfunction "PC_15_P$17") (pintype "bidirectional"))
    )
    (net (code "103") (name "unconnected-(U$3-RESET-PadP$4)") (class "Default")
      (node (ref "U$3") (pin "P$4") (pinfunction "RESET_P$4") (pintype "bidirectional"))
    )
    (net (code "104") (name "unconnected-(U$3-VBAT-PadP$20)") (class "Default")
      (node (ref "U$3") (pin "P$20") (pinfunction "VBAT_P$20") (pintype "bidirectional"))
    )
    (net (code "105") (name "unconnected-(U$4-DOUT-Pad2)") (class "Default")
      (node (ref "U$4") (pin "2") (pinfunction "DOUT_2") (pintype "bidirectional"))
    )
    (net (code "106") (name "unconnected-(U$4-OUT0-Pad26)") (class "Default")
      (node (ref "U$4") (pin "26") (pinfunction "OUT0_26") (pintype "bidirectional"))
    )
    (net (code "107") (name "unconnected-(U$4-OUT18-Pad4)") (class "Default")
      (node (ref "U$4") (pin "4") (pinfunction "OUT18_4") (pintype "bidirectional"))
    )
    (net (code "108") (name "unconnected-(U$4-OUT19-Pad3)") (class "Default")
      (node (ref "U$4") (pin "3") (pinfunction "OUT19_3") (pintype "bidirectional"))
    )
  )
)
